# photodiode_pcb.net
KiCad netlist of a schematic drawn in Altium Designer
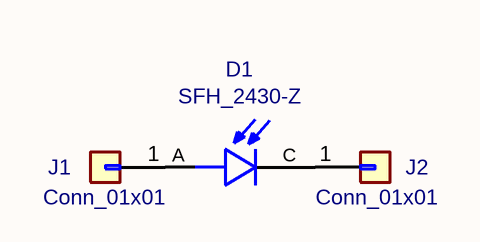
[diagram p0: photodiode_pcb.SchDoc]

(export (version "E")
  (design (tool "Eeschema 10.0.6"))
  (components
    (comp (ref "D1")
      (value "SFH_2430-Z")
      (fields (field (name "MANUFACTURER") "OSRAM"))
      (libsource (lib "SFH_2430-Z") (part "SFH_2430-Z"))
    )
    (comp (ref "J1") (value "Conn_01x01") (libsource (lib "Connector_Generic") (part "Conn_01x01")))
    (comp (ref "J2") (value "Conn_01x01") (libsource (lib "") (part "Conn_01x01_1")))
  )
  (nets
    (net (code "1") (name "Net-(J1-Pin_1)") (class "Default")
      (node (ref "D1") (pin "A") (pinfunction "A_A") (pintype "passive"))
      (node (ref "J1") (pin "1") (pinfunction "Pin_1_1") (pintype "passive"))
    )
    (net (code "2") (name "Net-(J2-Pin_1)") (class "Default")
      (node (ref "D1") (pin "C") (pinfunction "C_C") (pintype "passive"))
      (node (ref "J2") (pin "1") (pinfunction "Pin_1_1") (pintype "passive"))
    )
  )
)
